# TPS54340_PS_and_Load_Rev3.net
KiCad netlist of a schematic drawn in EAGLE
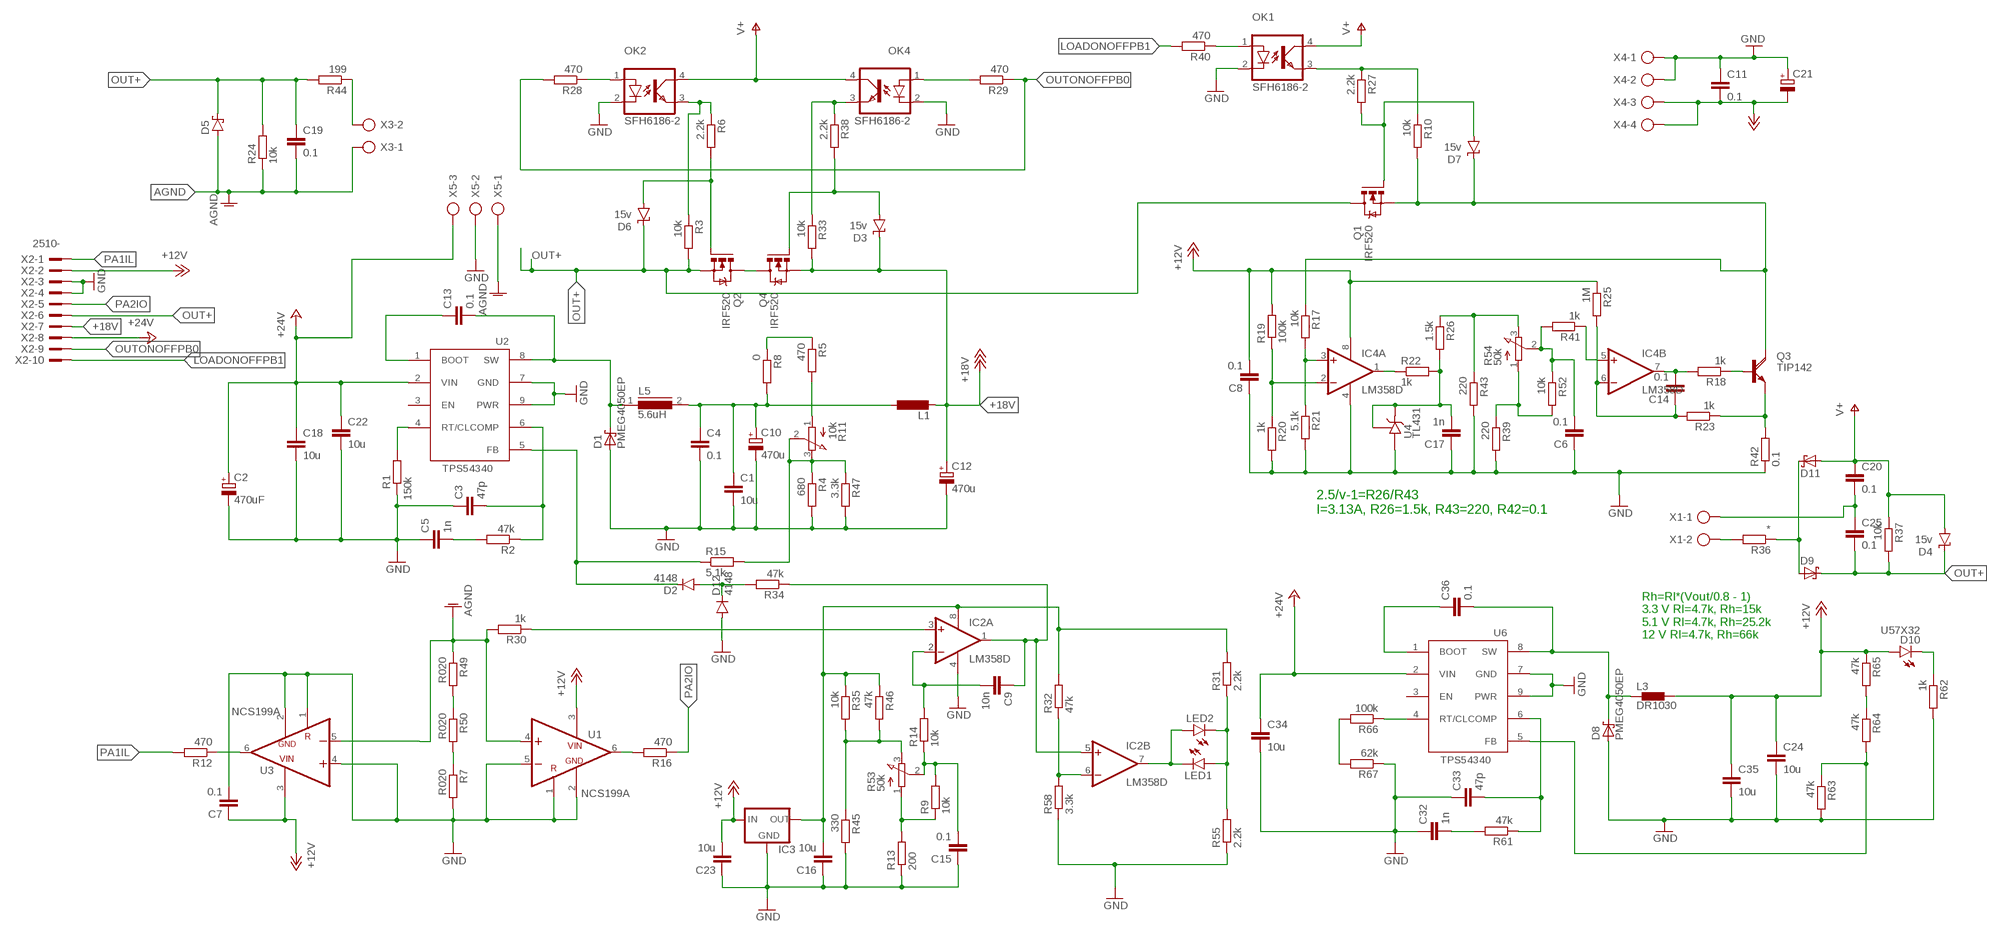
[diagram p0: schematic, sheet 1]

(export (version "E")
  (design (tool "Eeschema 10.0.6"))
  (components
    (comp (ref "C1")
      (value "10u")
      (footprint "eagle-import:C1210")
      (libsource (lib "eagle-import") (part "rcl_334_C-EUC1210"))
    )
    (comp (ref "C2")
      (value "470uF")
      (footprint "eagle-import:E5-10,5")
      (libsource (lib "eagle-import") (part "CPOL-EUE5-10.5"))
    )
    (comp (ref "C3")
      (value "47p")
      (footprint "eagle-import:C0603K")
      (libsource (lib "eagle-import") (part "rcl_334_C-EUC0603K"))
    )
    (comp (ref "C4")
      (value "0.1")
      (footprint "eagle-import:C1206")
      (libsource (lib "eagle-import") (part "C-EUC1206"))
    )
    (comp (ref "C5")
      (value "1n")
      (footprint "eagle-import:C0603K")
      (libsource (lib "eagle-import") (part "rcl_334_C-EUC0603K"))
    )
    (comp (ref "C6")
      (value "0.1")
      (footprint "eagle-import:C0603K")
      (libsource (lib "eagle-import") (part "rcl_334_C-EUC0603K"))
    )
    (comp (ref "C7")
      (value "0.1")
      (footprint "eagle-import:C0603K")
      (libsource (lib "eagle-import") (part "rcl_334_C-EUC0603K"))
    )
    (comp (ref "C8")
      (value "0.1")
      (footprint "eagle-import:C0603K")
      (libsource (lib "eagle-import") (part "rcl_334_C-EUC0603K"))
    )
    (comp (ref "C9")
      (value "10n")
      (footprint "eagle-import:C0603K")
      (libsource (lib "eagle-import") (part "rcl_334_C-EUC0603K"))
    )
    (comp (ref "C10")
      (value "470u")
      (footprint "eagle-import:E5-10,5")
      (libsource (lib "eagle-import") (part "CPOL-EUE5-10.5"))
    )
    (comp (ref "C11")
      (value "0.1")
      (footprint "eagle-import:C1206")
      (libsource (lib "eagle-import") (part "C-EUC1206"))
    )
    (comp (ref "C12")
      (value "470u")
      (footprint "eagle-import:E5-10,5")
      (libsource (lib "eagle-import") (part "CPOL-EUE5-10.5"))
    )
    (comp (ref "C13")
      (value "0.1")
      (footprint "eagle-import:C102-043X133")
      (libsource (lib "eagle-import") (part "rcl_334_C-EU102-043X133"))
    )
    (comp (ref "C14")
      (value "0.1")
      (footprint "eagle-import:C0603K")
      (libsource (lib "eagle-import") (part "rcl_334_C-EUC0603K"))
    )
    (comp (ref "C15")
      (value "0.1")
      (footprint "eagle-import:C0603K")
      (libsource (lib "eagle-import") (part "rcl_334_C-EUC0603K"))
    )
    (comp (ref "C16")
      (value "10u")
      (footprint "eagle-import:C0603K")
      (libsource (lib "eagle-import") (part "rcl_334_C-EUC0603K"))
    )
    (comp (ref "C17")
      (value "1n")
      (footprint "eagle-import:C0603K")
      (libsource (lib "eagle-import") (part "rcl_334_C-EUC0603K"))
    )
    (comp (ref "C18")
      (value "10u")
      (footprint "eagle-import:C1210")
      (libsource (lib "eagle-import") (part "rcl_334_C-EUC1210"))
    )
    (comp (ref "C19")
      (value "0.1")
      (footprint "eagle-import:C1206")
      (libsource (lib "eagle-import") (part "C-EUC1206"))
    )
    (comp (ref "C20")
      (value "0.1")
      (footprint "eagle-import:C1206")
      (libsource (lib "eagle-import") (part "C-EUC1206"))
    )
    (comp (ref "C21")
      (value "CPOL-EUE2.5-6")
      (footprint "eagle-import:E2,5-6")
      (libsource (lib "eagle-import") (part "CPOL-EUE2.5-6"))
    )
    (comp (ref "C22")
      (value "10u")
      (footprint "eagle-import:C1210")
      (libsource (lib "eagle-import") (part "rcl_334_C-EUC1210"))
    )
    (comp (ref "C23")
      (value "10u")
      (footprint "eagle-import:C0603K")
      (libsource (lib "eagle-import") (part "rcl_334_C-EUC0603K"))
    )
    (comp (ref "C24")
      (value "10u")
      (footprint "eagle-import:C1210")
      (libsource (lib "eagle-import") (part "rcl_334_C-EUC1210"))
    )
    (comp (ref "C25")
      (value "0.1")
      (footprint "eagle-import:C1206")
      (libsource (lib "eagle-import") (part "C-EUC1206"))
    )
    (comp (ref "C32")
      (value "1n")
      (footprint "eagle-import:C0603K")
      (libsource (lib "eagle-import") (part "rcl_334_C-EUC0603K"))
    )
    (comp (ref "C33")
      (value "47p")
      (footprint "eagle-import:C0603K")
      (libsource (lib "eagle-import") (part "rcl_334_C-EUC0603K"))
    )
    (comp (ref "C34")
      (value "10u")
      (footprint "eagle-import:C1210")
      (libsource (lib "eagle-import") (part "rcl_334_C-EUC1210"))
    )
    (comp (ref "C35")
      (value "10u")
      (footprint "eagle-import:C1206")
      (libsource (lib "eagle-import") (part "C-EUC1206"))
    )
    (comp (ref "C36")
      (value "0.1")
      (footprint "eagle-import:C102-043X133")
      (libsource (lib "eagle-import") (part "rcl_334_C-EU102-043X133"))
    )
    (comp (ref "D1")
      (value "PMEG4050EP")
      (footprint "eagle-import:SOD128")
      (libsource (lib "eagle-import") (part "PMEG4050EP"))
    )
    (comp (ref "D2")
      (value "4148")
      (footprint "eagle-import:SOD80C")
      (libsource (lib "eagle-import") (part "PMLL41SOD80C"))
    )
    (comp (ref "D3")
      (value "15v")
      (footprint "eagle-import:SMBJ")
      (libsource (lib "eagle-import") (part "SUPPRESSOR-SMBJ"))
    )
    (comp (ref "D4")
      (value "15v")
      (footprint "eagle-import:SMBJ")
      (libsource (lib "eagle-import") (part "SUPPRESSOR-SMBJ"))
    )
    (comp (ref "D5")
      (value "SCHOTTKY-DIODESMD")
      (footprint "eagle-import:SMB")
      (libsource (lib "eagle-import") (part "SCHOTTKY-DIODESMD"))
    )
    (comp (ref "D6")
      (value "15v")
      (footprint "eagle-import:SMBJ")
      (libsource (lib "eagle-import") (part "SUPPRESSOR-SMBJ"))
    )
    (comp (ref "D7")
      (value "15v")
      (footprint "eagle-import:SMBJ")
      (libsource (lib "eagle-import") (part "SUPPRESSOR-SMBJ"))
    )
    (comp (ref "D8")
      (value "PMEG4050EP")
      (footprint "eagle-import:SOD128")
      (libsource (lib "eagle-import") (part "PMEG4050EP"))
    )
    (comp (ref "D9")
      (value "PMEG4050EP")
      (footprint "eagle-import:SOD128")
      (libsource (lib "eagle-import") (part "PMEG4050EP"))
    )
    (comp (ref "D10")
      (value "U57X32")
      (footprint "eagle-import:U57X32")
      (libsource (lib "eagle-import") (part "U57X32"))
    )
    (comp (ref "D11")
      (value "PMEG4050EP")
      (footprint "eagle-import:SOD128")
      (libsource (lib "eagle-import") (part "PMEG4050EP"))
    )
    (comp (ref "D12")
      (value "4148")
      (footprint "eagle-import:SOD80C")
      (libsource (lib "eagle-import") (part "PMLL41SOD80C"))
    )
    (comp (ref "IC2")
      (value "LM358D")
      (footprint "eagle-import:SO08")
      (libsource (lib "eagle-import") (part "LM358D"))
    )
    (comp (ref "IC3")
      (value "LM1117")
      (footprint "eagle-import:SOT223")
      (libsource (lib "eagle-import") (part "LM1117"))
    )
    (comp (ref "IC4")
      (value "LM358D")
      (footprint "eagle-import:SO08")
      (libsource (lib "eagle-import") (part "LM358D"))
    )
    (comp (ref "L1")
      (value "L-EU0207/5V")
      (footprint "eagle-import:0207_5V")
      (libsource (lib "eagle-import") (part "L-EU0207/5V"))
    )
    (comp (ref "L3")
      (value "DR1030")
      (footprint "eagle-import:DR1030")
      (libsource (lib "eagle-import") (part "DR1030"))
    )
    (comp (ref "L5")
      (value "5.6uH")
      (footprint "eagle-import:DR125")
      (libsource (lib "eagle-import") (part "DR125"))
    )
    (comp (ref "LED1")
      (value "LEDB152")
      (footprint "eagle-import:Q62902-B152")
      (libsource (lib "eagle-import") (part "LEDB152"))
    )
    (comp (ref "LED2")
      (value "LEDB152")
      (footprint "eagle-import:Q62902-B152")
      (libsource (lib "eagle-import") (part "LEDB152"))
    )
    (comp (ref "OK1")
      (value "SFH6186-2")
      (footprint "eagle-import:SMD4-7")
      (fields (field (name "MF") "VISHAY/TELEFUNKEN"))
      (libsource (lib "eagle-import") (part "SFH618?6-2"))
    )
    (comp (ref "OK2")
      (value "SFH6186-2")
      (footprint "eagle-import:SMD4-7")
      (fields (field (name "MF") "VISHAY/TELEFUNKEN"))
      (libsource (lib "eagle-import") (part "SFH618?6-2"))
    )
    (comp (ref "OK4")
      (value "SFH6186-2")
      (footprint "eagle-import:SMD4-7")
      (fields (field (name "MF") "VISHAY/TELEFUNKEN"))
      (libsource (lib "eagle-import") (part "SFH618?6-2"))
    )
    (comp (ref "Q1")
      (value "IRF520")
      (footprint "eagle-import:TO220BV")
      (libsource (lib "eagle-import") (part "IRF520"))
    )
    (comp (ref "Q2")
      (value "IRF520")
      (footprint "eagle-import:TO220BV")
      (libsource (lib "eagle-import") (part "IRF520"))
    )
    (comp (ref "Q3")
      (value "TIP142")
      (footprint "eagle-import:SOT93")
      (libsource (lib "eagle-import") (part "TIP142"))
    )
    (comp (ref "Q4")
      (value "IRF520")
      (footprint "eagle-import:TO220BV")
      (libsource (lib "eagle-import") (part "IRF520"))
    )
    (comp (ref "R1")
      (value "150k")
      (footprint "eagle-import:R1206")
      (libsource (lib "eagle-import") (part "R-EU_R1206"))
    )
    (comp (ref "R2")
      (value "47k")
      (footprint "eagle-import:R0603")
      (libsource (lib "eagle-import") (part "rcl_334_R-EU_R0603"))
    )
    (comp (ref "R3")
      (value "10k")
      (footprint "eagle-import:R0603")
      (libsource (lib "eagle-import") (part "rcl_334_R-EU_R0603"))
    )
    (comp (ref "R4")
      (value "680")
      (footprint "eagle-import:R1206")
      (libsource (lib "eagle-import") (part "R-EU_R1206"))
    )
    (comp (ref "R5")
      (value "470")
      (footprint "eagle-import:R1206")
      (libsource (lib "eagle-import") (part "R-EU_R1206"))
    )
    (comp (ref "R6")
      (value "2.2k")
      (footprint "eagle-import:R0603")
      (libsource (lib "eagle-import") (part "rcl_334_R-EU_R0603"))
    )
    (comp (ref "R7")
      (value "R020")
      (footprint "eagle-import:R1206")
      (libsource (lib "eagle-import") (part "R-EU_R1206"))
    )
    (comp (ref "R8")
      (value "0")
      (footprint "eagle-import:R0603")
      (libsource (lib "eagle-import") (part "rcl_334_R-EU_R0603"))
    )
    (comp (ref "R9")
      (value "10k")
      (footprint "eagle-import:R0603")
      (libsource (lib "eagle-import") (part "rcl_334_R-EU_R0603"))
    )
    (comp (ref "R10")
      (value "10k")
      (footprint "eagle-import:R0603")
      (libsource (lib "eagle-import") (part "rcl_334_R-EU_R0603"))
    )
    (comp (ref "R11")
      (value "10k")
      (footprint "eagle-import:3RP_1610N")
      (libsource (lib "eagle-import") (part "3RP/1610N"))
    )
    (comp (ref "R12")
      (value "470")
      (footprint "eagle-import:R0603")
      (libsource (lib "eagle-import") (part "rcl_334_R-EU_R0603"))
    )
    (comp (ref "R13")
      (value "200")
      (footprint "eagle-import:R0603")
      (libsource (lib "eagle-import") (part "rcl_334_R-EU_R0603"))
    )
    (comp (ref "R14")
      (value "10k")
      (footprint "eagle-import:R1206")
      (libsource (lib "eagle-import") (part "R-EU_R1206"))
    )
    (comp (ref "R15")
      (value "5.1k")
      (footprint "eagle-import:R0603")
      (libsource (lib "eagle-import") (part "rcl_334_R-EU_R0603"))
    )
    (comp (ref "R16")
      (value "470")
      (footprint "eagle-import:R1206")
      (libsource (lib "eagle-import") (part "R-EU_R1206"))
    )
    (comp (ref "R17")
      (value "10k")
      (footprint "eagle-import:R0603")
      (libsource (lib "eagle-import") (part "rcl_334_R-EU_R0603"))
    )
    (comp (ref "R18")
      (value "1k")
      (footprint "eagle-import:R0603")
      (libsource (lib "eagle-import") (part "rcl_334_R-EU_R0603"))
    )
    (comp (ref "R19")
      (value "100k")
      (footprint "eagle-import:R1206")
      (libsource (lib "eagle-import") (part "R-EU_R1206"))
    )
    (comp (ref "R20")
      (value "1k")
      (footprint "eagle-import:R0603")
      (libsource (lib "eagle-import") (part "rcl_334_R-EU_R0603"))
    )
    (comp (ref "R21")
      (value "5.1k")
      (footprint "eagle-import:R0603")
      (libsource (lib "eagle-import") (part "rcl_334_R-EU_R0603"))
    )
    (comp (ref "R22")
      (value "1k")
      (footprint "eagle-import:R0603")
      (libsource (lib "eagle-import") (part "rcl_334_R-EU_R0603"))
    )
    (comp (ref "R23")
      (value "1k")
      (footprint "eagle-import:R0603")
      (libsource (lib "eagle-import") (part "rcl_334_R-EU_R0603"))
    )
    (comp (ref "R24")
      (value "10k")
      (footprint "eagle-import:R1206")
      (libsource (lib "eagle-import") (part "R-EU_R1206"))
    )
    (comp (ref "R25")
      (value "1M")
      (footprint "eagle-import:R1206")
      (libsource (lib "eagle-import") (part "R-EU_R1206"))
    )
    (comp (ref "R26")
      (value "1.5k")
      (footprint "eagle-import:R0603")
      (libsource (lib "eagle-import") (part "rcl_334_R-EU_R0603"))
    )
    (comp (ref "R27")
      (value "2.2k")
      (footprint "eagle-import:R0603")
      (libsource (lib "eagle-import") (part "rcl_334_R-EU_R0603"))
    )
    (comp (ref "R28")
      (value "470")
      (footprint "eagle-import:R0603")
      (libsource (lib "eagle-import") (part "rcl_334_R-EU_R0603"))
    )
    (comp (ref "R29")
      (value "470")
      (footprint "eagle-import:R0603")
      (libsource (lib "eagle-import") (part "rcl_334_R-EU_R0603"))
    )
    (comp (ref "R30")
      (value "1k")
      (footprint "eagle-import:R0603")
      (libsource (lib "eagle-import") (part "rcl_334_R-EU_R0603"))
    )
    (comp (ref "R31")
      (value "2.2k")
      (footprint "eagle-import:R0603")
      (libsource (lib "eagle-import") (part "rcl_334_R-EU_R0603"))
    )
    (comp (ref "R32")
      (value "47k")
      (footprint "eagle-import:R0603")
      (libsource (lib "eagle-import") (part "rcl_334_R-EU_R0603"))
    )
    (comp (ref "R33")
      (value "10k")
      (footprint "eagle-import:R0603")
      (libsource (lib "eagle-import") (part "rcl_334_R-EU_R0603"))
    )
    (comp (ref "R34")
      (value "47k")
      (footprint "eagle-import:R0603")
      (libsource (lib "eagle-import") (part "rcl_334_R-EU_R0603"))
    )
    (comp (ref "R35")
      (value "10k")
      (footprint "eagle-import:R0603")
      (libsource (lib "eagle-import") (part "rcl_334_R-EU_R0603"))
    )
    (comp (ref "R36")
      (value "*")
      (footprint "eagle-import:R1206")
      (libsource (lib "eagle-import") (part "R-EU_R1206"))
    )
    (comp (ref "R37")
      (value "10k")
      (footprint "eagle-import:R1206")
      (libsource (lib "eagle-import") (part "R-EU_R1206"))
    )
    (comp (ref "R38")
      (value "2.2k")
      (footprint "eagle-import:R0603")
      (libsource (lib "eagle-import") (part "rcl_334_R-EU_R0603"))
    )
    (comp (ref "R39")
      (value "220")
      (footprint "eagle-import:R0603")
      (libsource (lib "eagle-import") (part "rcl_334_R-EU_R0603"))
    )
    (comp (ref "R40")
      (value "470")
      (footprint "eagle-import:R0603")
      (libsource (lib "eagle-import") (part "rcl_334_R-EU_R0603"))
    )
    (comp (ref "R41")
      (value "1k")
      (footprint "eagle-import:R1206")
      (libsource (lib "eagle-import") (part "R-EU_R1206"))
    )
    (comp (ref "R42")
      (value "0.1")
      (footprint "eagle-import:0414_15")
      (libsource (lib "eagle-import") (part "rcl_334_R-EU_0414/15"))
    )
    (comp (ref "R43")
      (value "220")
      (footprint "eagle-import:R0603")
      (libsource (lib "eagle-import") (part "rcl_334_R-EU_R0603"))
    )
    (comp (ref "R44")
      (value "199")
      (footprint "eagle-import:R0603")
      (libsource (lib "eagle-import") (part "rcl_334_R-EU_R0603"))
    )
    (comp (ref "R45")
      (value "330")
      (footprint "eagle-import:R0603")
      (libsource (lib "eagle-import") (part "rcl_334_R-EU_R0603"))
    )
    (comp (ref "R46")
      (value "47k")
      (footprint "eagle-import:R0603")
      (libsource (lib "eagle-import") (part "rcl_334_R-EU_R0603"))
    )
    (comp (ref "R47")
      (value "3.3k")
      (footprint "eagle-import:R1206")
      (libsource (lib "eagle-import") (part "R-EU_R1206"))
    )
    (comp (ref "R49")
      (value "R020")
      (footprint "eagle-import:R1206")
      (libsource (lib "eagle-import") (part "R-EU_R1206"))
    )
    (comp (ref "R50")
      (value "R020")
      (footprint "eagle-import:R1206")
      (libsource (lib "eagle-import") (part "R-EU_R1206"))
    )
    (comp (ref "R52")
      (value "10k")
      (footprint "eagle-import:R0603")
      (libsource (lib "eagle-import") (part "rcl_334_R-EU_R0603"))
    )
    (comp (ref "R53")
      (value "50k")
      (footprint "eagle-import:3RP_1610N")
      (libsource (lib "eagle-import") (part "3RP/1610N"))
    )
    (comp (ref "R54")
      (value "50k")
      (footprint "eagle-import:3RP_1610N")
      (libsource (lib "eagle-import") (part "3RP/1610N"))
    )
    (comp (ref "R55")
      (value "2.2k")
      (footprint "eagle-import:R0603")
      (libsource (lib "eagle-import") (part "rcl_334_R-EU_R0603"))
    )
    (comp (ref "R58")
      (value "3.3k")
      (footprint "eagle-import:R0603")
      (libsource (lib "eagle-import") (part "rcl_334_R-EU_R0603"))
    )
    (comp (ref "R61")
      (value "47k")
      (footprint "eagle-import:R0603")
      (libsource (lib "eagle-import") (part "rcl_334_R-EU_R0603"))
    )
    (comp (ref "R62")
      (value "1k")
      (footprint "eagle-import:R0603")
      (libsource (lib "eagle-import") (part "rcl_334_R-EU_R0603"))
    )
    (comp (ref "R63")
      (value "47k")
      (footprint "eagle-import:R0603")
      (libsource (lib "eagle-import") (part "rcl_334_R-EU_R0603"))
    )
    (comp (ref "R64")
      (value "47k")
      (footprint "eagle-import:R0603")
      (libsource (lib "eagle-import") (part "rcl_334_R-EU_R0603"))
    )
    (comp (ref "R65")
      (value "47k")
      (footprint "eagle-import:R0603")
      (libsource (lib "eagle-import") (part "rcl_334_R-EU_R0603"))
    )
    (comp (ref "R66")
      (value "100k")
      (footprint "eagle-import:R0603")
      (libsource (lib "eagle-import") (part "rcl_334_R-EU_R0603"))
    )
    (comp (ref "R67")
      (value "62k")
      (footprint "eagle-import:R0603")
      (libsource (lib "eagle-import") (part "rcl_334_R-EU_R0603"))
    )
    (comp (ref "U1")
      (value "NCS199A")
      (footprint "eagle-import:SOT363")
      (libsource (lib "eagle-import") (part "NCS199A"))
    )
    (comp (ref "U2")
      (value "TPS54340")
      (footprint "eagle-import:HSOP")
      (libsource (lib "eagle-import") (part "TPS54340SO8"))
    )
    (comp (ref "U3")
      (value "NCS199A")
      (footprint "eagle-import:SOT363")
      (libsource (lib "eagle-import") (part "NCS199A"))
    )
    (comp (ref "U4")
      (value "TL431")
      (footprint "eagle-import:SOT23")
      (libsource (lib "eagle-import") (part "TL431"))
    )
    (comp (ref "U6")
      (value "TPS54340SO8")
      (footprint "eagle-import:HSOP")
      (libsource (lib "eagle-import") (part "TPS54340SO8"))
    )
    (comp (ref "X1")
      (value "AK500/2")
      (footprint "eagle-import:AK500_2")
      (libsource (lib "eagle-import") (part "AK500/2"))
    )
    (comp (ref "X2")
      (value "2510-")
      (footprint "eagle-import:PAK100_2500-10")
      (fields (field (name "MF") "3M") (field (name "MPN") "2510-6002UB"))
      (libsource (lib "eagle-import") (part "2510-"))
    )
    (comp (ref "X3")
      (value "AK500/2")
      (footprint "eagle-import:AK500_2")
      (libsource (lib "eagle-import") (part "AK500/2"))
    )
    (comp (ref "X4")
      (value "AK500/4")
      (footprint "eagle-import:AK500_4")
      (libsource (lib "eagle-import") (part "AK500/4"))
    )
    (comp (ref "X5")
      (value "AK500/3")
      (footprint "eagle-import:AK500_3")
      (libsource (lib "eagle-import") (part "AK500/3"))
    )
  )
  (nets
    (net (code "1") (name "+12V") (class "Default")
      (node (ref "C11") (pin "2") (pinfunction "2_2") (pintype "passive"))
      (node (ref "C21") (pin "-") (pinfunction "-_-") (pintype "passive"))
      (node (ref "C23") (pin "2") (pinfunction "2_2") (pintype "passive"))
      (node (ref "C24") (pin "1") (pinfunction "1_1") (pintype "passive"))
      (node (ref "C35") (pin "1") (pinfunction "1_1") (pintype "passive"))
      (node (ref "C7") (pin "1") (pinfunction "1_1") (pintype "passive"))
      (node (ref "C8") (pin "2") (pinfunction "2_2") (pintype "passive"))
      (node (ref "D10") (pin "A") (pinfunction "A_A") (pintype "passive"))
      (node (ref "IC3") (pin "3") (pinfunction "IN_3") (pintype "input"))
      (node (ref "IC4") (pin "8") (pinfunction "V+_8") (pintype "power_in"))
      (node (ref "L3") (pin "2") (pinfunction "2_2") (pintype "passive"))
      (node (ref "R19") (pin "2") (pinfunction "2_2") (pintype "passive"))
      (node (ref "R25") (pin "1") (pinfunction "1_1") (pintype "passive"))
      (node (ref "R65") (pin "1") (pinfunction "1_1") (pintype "passive"))
      (node (ref "U1") (pin "3") (pinfunction "VCC_3") (pintype "power_in"))
      (node (ref "U3") (pin "3") (pinfunction "VCC_3") (pintype "power_in"))
      (node (ref "X2") (pin "2") (pinfunction "KL_2") (pintype "passive"))
      (node (ref "X4") (pin "3") (pinfunction "KL_3") (pintype "passive"))
      (node (ref "X4") (pin "4") (pinfunction "KL_4") (pintype "passive"))
    )
    (net (code "2") (name "+18V") (class "Default")
      (node (ref "C12") (pin "+") (pinfunction "+_+") (pintype "passive"))
      (node (ref "D3") (pin "C") (pinfunction "C_C") (pintype "passive"))
      (node (ref "L1") (pin "2") (pinfunction "2_2") (pintype "passive"))
      (node (ref "Q4") (pin "S") (pinfunction "S_S") (pintype "passive"))
      (node (ref "R33") (pin "2") (pinfunction "2_2") (pintype "passive"))
      (node (ref "X2") (pin "7") (pinfunction "KL_7") (pintype "passive"))
    )
    (net (code "3") (name "+24V") (class "Default")
      (node (ref "C18") (pin "1") (pinfunction "1_1") (pintype "passive"))
      (node (ref "C2") (pin "+") (pinfunction "+_+") (pintype "passive"))
      (node (ref "C22") (pin "1") (pinfunction "1_1") (pintype "passive"))
      (node (ref "C34") (pin "1") (pinfunction "1_1") (pintype "passive"))
      (node (ref "U2") (pin "2") (pinfunction "VIN_2") (pintype "power_in"))
      (node (ref "U6") (pin "2") (pinfunction "VIN_2") (pintype "power_in"))
      (node (ref "X2") (pin "8") (pinfunction "KL_8") (pintype "passive"))
      (node (ref "X5") (pin "3") (pinfunction "KL_3") (pintype "passive"))
    )
    (net (code "4") (name "AGND") (class "Default")
      (node (ref "C19") (pin "2") (pinfunction "2_2") (pintype "passive"))
      (node (ref "D5") (pin "A") (pinfunction "A_A") (pintype "passive"))
      (node (ref "R24") (pin "1") (pinfunction "1_1") (pintype "passive"))
      (node (ref "R30") (pin "2") (pinfunction "2_2") (pintype "passive"))
      (node (ref "R49") (pin "1") (pinfunction "1_1") (pintype "passive"))
      (node (ref "U1") (pin "4") (pinfunction "IN+_4") (pintype "input"))
      (node (ref "U3") (pin "5") (pinfunction "IN-_5") (pintype "input"))
      (node (ref "X3") (pin "1") (pinfunction "KL_1") (pintype "passive"))
      (node (ref "X5") (pin "1") (pinfunction "KL_1") (pintype "passive"))
    )
    (net (code "5") (name "GND") (class "Default")
      (node (ref "C1") (pin "2") (pinfunction "2_2") (pintype "passive"))
      (node (ref "C10") (pin "-") (pinfunction "-_-") (pintype "passive"))
      (node (ref "C11") (pin "1") (pinfunction "1_1") (pintype "passive"))
      (node (ref "C12") (pin "-") (pinfunction "-_-") (pintype "passive"))
      (node (ref "C15") (pin "1") (pinfunction "1_1") (pintype "passive"))
      (node (ref "C16") (pin "1") (pinfunction "1_1") (pintype "passive"))
      (node (ref "C17") (pin "1") (pinfunction "1_1") (pintype "passive"))
      (node (ref "C18") (pin "2") (pinfunction "2_2") (pintype "passive"))
      (node (ref "C2") (pin "-") (pinfunction "-_-") (pintype "passive"))
      (node (ref "C21") (pin "+") (pinfunction "+_+") (pintype "passive"))
      (node (ref "C22") (pin "2") (pinfunction "2_2") (pintype "passive"))
      (node (ref "C23") (pin "1") (pinfunction "1_1") (pintype "passive"))
      (node (ref "C24") (pin "2") (pinfunction "2_2") (pintype "passive"))
      (node (ref "C3") (pin "1") (pinfunction "1_1") (pintype "passive"))
      (node (ref "C32") (pin "1") (pinfunction "1_1") (pintype "passive"))
      (node (ref "C33") (pin "1") (pinfunction "1_1") (pintype "passive"))
      (node (ref "C34") (pin "2") (pinfunction "2_2") (pintype "passive"))
      (node (ref "C35") (pin "2") (pinfunction "2_2") (pintype "passive"))
      (node (ref "C4") (pin "2") (pinfunction "2_2") (pintype "passive"))
      (node (ref "C5") (pin "1") (pinfunction "1_1") (pintype "passive"))
      (node (ref "C6") (pin "1") (pinfunction "1_1") (pintype "passive"))
      (node (ref "C7") (pin "2") (pinfunction "2_2") (pintype "passive"))
      (node (ref "C8") (pin "1") (pinfunction "1_1") (pintype "passive"))
      (node (ref "D1") (pin "2") (pinfunction "A_2") (pintype "passive"))
      (node (ref "D12") (pin "A") (pinfunction "A_A") (pintype "passive"))
      (node (ref "D8") (pin "2") (pinfunction "A_2") (pintype "passive"))
      (node (ref "IC2") (pin "4") (pinfunction "V-_4") (pintype "power_in"))
      (node (ref "IC3") (pin "1") (pinfunction "GND_1") (pintype "input"))
      (node (ref "IC4") (pin "4") (pinfunction "V-_4") (pintype "power_in"))
      (node (ref "OK1") (pin "2") (pinfunction "C_2") (pintype "passive"))
      (node (ref "OK2") (pin "2") (pinfunction "C_2") (pintype "passive"))
      (node (ref "OK4") (pin "2") (pinfunction "C_2") (pintype "passive"))
      (node (ref "R1") (pin "1") (pinfunction "1_1") (pintype "passive"))
      (node (ref "R13") (pin "1") (pinfunction "1_1") (pintype "passive"))
      (node (ref "R20") (pin "2") (pinfunction "2_2") (pintype "passive"))
      (node (ref "R21") (pin "2") (pinfunction "2_2") (pintype "passive"))
      (node (ref "R39") (pin "2") (pinfunction "2_2") (pintype "passive"))
      (node (ref "R4") (pin "2") (pinfunction "2_2") (pintype "passive"))
      (node (ref "R42") (pin "1") (pinfunction "1_1") (pintype "passive"))
      (node (ref "R43") (pin "2") (pinfunction "2_2") (pintype "passive"))
      (node (ref "R45") (pin "2") (pinfunction "2_2") (pintype "passive"))
      (node (ref "R47") (pin "2") (pinfunction "2_2") (pintype "passive"))
      (node (ref "R55") (pin "1") (pinfunction "1_1") (pintype "passive"))
      (node (ref "R58") (pin "1") (pinfunction "1_1") (pintype "passive"))
      (node (ref "R62") (pin "2") (pinfunction "2_2") (pintype "passive"))
      (node (ref "R63") (pin "2") (pinfunction "2_2") (pintype "passive"))
      (node (ref "R67") (pin "1") (pinfunction "1_1") (pintype "passive"))
      (node (ref "R7") (pin "2") (pinfunction "2_2") (pintype "passive"))
      (node (ref "U1") (pin "1") (pinfunction "REF_1") (pintype "input"))
      (node (ref "U1") (pin "2") (pinfunction "GND_2") (pintype "power_in"))
      (node (ref "U1") (pin "5") (pinfunction "IN-_5") (pintype "input"))
      (node (ref "U2") (pin "7") (pinfunction "GND_7") (pintype "power_in"))
      (node (ref "U2") (pin "9") (pinfunction "PWR_9") (pintype "power_in"))
      (node (ref "U3") (pin "1") (pinfunction "REF_1") (pintype "input"))
      (node (ref "U3") (pin "2") (pinfunction "GND_2") (pintype "power_in"))
      (node (ref "U3") (pin "4") (pinfunction "IN+_4") (pintype "input"))
      (node (ref "U4") (pin "3") (pinfunction "A_3") (pintype "passive"))
      (node (ref "U6") (pin "7") (pinfunction "GND_7") (pintype "power_in"))
      (node (ref "U6") (pin "9") (pinfunction "PWR_9") (pintype "power_in"))
      (node (ref "X2") (pin "3") (pinfunction "KL_3") (pintype "passive"))
      (node (ref "X2") (pin "4") (pinfunction "KL_4") (pintype "passive"))
      (node (ref "X4") (pin "1") (pinfunction "KL_1") (pintype "passive"))
      (node (ref "X4") (pin "2") (pinfunction "KL_2") (pintype "passive"))
      (node (ref "X5") (pin "2") (pinfunction "KL_2") (pintype "passive"))
    )
    (net (code "6") (name "LOADONOFFPB1") (class "Default")
      (node (ref "R40") (pin "2") (pinfunction "2_2") (pintype "passive"))
      (node (ref "X2") (pin "10") (pinfunction "KL_10") (pintype "passive"))
    )
    (net (code "7") (name "Net-(C1-Pad1)") (class "Default")
      (node (ref "C1") (pin "1") (pinfunction "1_1") (pintype "passive"))
      (node (ref "C10") (pin "+") (pinfunction "+_+") (pintype "passive"))
      (node (ref "C4") (pin "1") (pinfunction "1_1") (pintype "passive"))
      (node (ref "L1") (pin "1") (pinfunction "1_1") (pintype "passive"))
      (node (ref "L5") (pin "2") (pinfunction "2_2") (pintype "passive"))
      (node (ref "R8") (pin "2") (pinfunction "2_2") (pintype "passive"))
    )
    (net (code "8") (name "Net-(C5-Pad2)") (class "Default")
      (node (ref "C5") (pin "2") (pinfunction "2_2") (pintype "passive"))
      (node (ref "R2") (pin "2") (pinfunction "2_2") (pintype "passive"))
    )
    (net (code "9") (name "Net-(C32-Pad2)") (class "Default")
      (node (ref "C32") (pin "2") (pinfunction "2_2") (pintype "passive"))
      (node (ref "R61") (pin "2") (pinfunction "2_2") (pintype "passive"))
    )
    (net (code "10") (name "Net-(D1-K)") (class "Default")
      (node (ref "C13") (pin "2") (pinfunction "2_2") (pintype "passive"))
      (node (ref "D1") (pin "1") (pinfunction "K_1") (pintype "passive"))
      (node (ref "L5") (pin "1") (pinfunction "1_1") (pintype "passive"))
      (node (ref "U2") (pin "8") (pinfunction "SW_8") (pintype "power_in"))
    )
    (net (code "11") (name "Net-(D3-PadA)") (class "Default")
      (node (ref "D3") (pin "A") (pinfunction "A_A") (pintype "passive"))
      (node (ref "Q4") (pin "G") (pinfunction "G_G") (pintype "passive"))
      (node (ref "R38") (pin "2") (pinfunction "2_2") (pintype "passive"))
    )
    (net (code "12") (name "Net-(D6-PadA)") (class "Default")
      (node (ref "D6") (pin "A") (pinfunction "A_A") (pintype "passive"))
      (node (ref "Q2") (pin "G") (pinfunction "G_G") (pintype "passive"))
      (node (ref "R6") (pin "2") (pinfunction "2_2") (pintype "passive"))
    )
    (net (code "13") (name "Net-(D7-PadA)") (class "Default")
      (node (ref "D7") (pin "A") (pinfunction "A_A") (pintype "passive"))
      (node (ref "Q1") (pin "G") (pinfunction "G_G") (pintype "passive"))
      (node (ref "R27") (pin "2") (pinfunction "2_2") (pintype "passive"))
    )
    (net (code "14") (name "Net-(D7-PadC)") (class "Default")
      (node (ref "D7") (pin "C") (pinfunction "C_C") (pintype "passive"))
      (node (ref "Q1") (pin "S") (pinfunction "S_S") (pintype "passive"))
      (node (ref "Q3") (pin "C") (pinfunction "C_C") (pintype "passive"))
      (node (ref "R10") (pin "2") (pinfunction "2_2") (pintype "passive"))
      (node (ref "R17") (pin "1") (pinfunction "1_1") (pintype "passive"))
    )
    (net (code "15") (name "Net-(D8-K)") (class "Default")
      (node (ref "C36") (pin "2") (pinfunction "2_2") (pintype "passive"))
      (node (ref "D8") (pin "1") (pinfunction "K_1") (pintype "passive"))
      (node (ref "L3") (pin "1") (pinfunction "1_1") (pintype "passive"))
      (node (ref "U6") (pin "8") (pinfunction "SW_8") (pintype "power_in"))
    )
    (net (code "16") (name "Net-(D10-C)") (class "Default")
      (node (ref "D10") (pin "K") (pinfunction "C_K") (pintype "passive"))
      (node (ref "R62") (pin "1") (pinfunction "1_1") (pintype "passive"))
    )
    (net (code "17") (name "Net-(D11-K)") (class "Default")
      (node (ref "D11") (pin "1") (pinfunction "K_1") (pintype "passive"))
      (node (ref "D9") (pin "2") (pinfunction "A_2") (pintype "passive"))
      (node (ref "R36") (pin "1") (pinfunction "1_1") (pintype "passive"))
    )
    (net (code "18") (name "Net-(D12-PadC)") (class "Default")
      (node (ref "D12") (pin "C") (pinfunction "C_C") (pintype "passive"))
      (node (ref "D2") (pin "A") (pinfunction "A_A") (pintype "passive"))
      (node (ref "R34") (pin "2") (pinfunction "2_2") (pintype "passive"))
    )
    (net (code "19") (name "Net-(IC2A-+IN)") (class "Default")
      (node (ref "IC2") (pin "3") (pinfunction "+IN_3") (pintype "input"))
      (node (ref "R30") (pin "1") (pinfunction "1_1") (pintype "passive"))
    )
    (net (code "20") (name "Net-(IC2A--IN)") (class "Default")
      (node (ref "C9") (pin "2") (pinfunction "2_2") (pintype "passive"))
      (node (ref "IC2") (pin "2") (pinfunction "-IN_2") (pintype "input"))
      (node (ref "R14") (pin "2") (pinfunction "2_2") (pintype "passive"))
    )
    (net (code "21") (name "Net-(IC2A-OUT)") (class "Default")
      (node (ref "C9") (pin "1") (pinfunction "1_1") (pintype "passive"))
      (node (ref "IC2") (pin "1") (pinfunction "OUT_1") (pintype "output"))
      (node (ref "IC2") (pin "5") (pinfunction "+IN_5") (pintype "input"))
      (node (ref "R34") (pin "1") (pinfunction "1_1") (pintype "passive"))
    )
    (net (code "22") (name "Net-(IC2B--IN)") (class "Default")
      (node (ref "IC2") (pin "6") (pinfunction "-IN_6") (pintype "input"))
      (node (ref "R32") (pin "1") (pinfunction "1_1") (pintype "passive"))
      (node (ref "R58") (pin "2") (pinfunction "2_2") (pintype "passive"))
    )
    (net (code "23") (name "Net-(IC2B-OUT)") (class "Default")
      (node (ref "IC2") (pin "7") (pinfunction "OUT_7") (pintype "output"))
      (node (ref "LED1") (pin "K") (pinfunction "C_K") (pintype "passive"))
      (node (ref "LED2") (pin "A") (pinfunction "A_A") (pintype "passive"))
    )
    (net (code "24") (name "Net-(IC2C-V+)") (class "Default")
      (node (ref "C16") (pin "2") (pinfunction "2_2") (pintype "passive"))
      (node (ref "IC2") (pin "8") (pinfunction "V+_8") (pintype "power_in"))
      (node (ref "IC3") (pin "2") (pinfunction "OUT_2") (pintype "passive"))
      (node (ref "IC3") (pin "4") (pinfunction "OUT_4") (pintype "passive"))
      (node (ref "R31") (pin "2") (pinfunction "2_2") (pintype "passive"))
      (node (ref "R32") (pin "2") (pinfunction "2_2") (pintype "passive"))
      (node (ref "R35") (pin "1") (pinfunction "1_1") (pintype "passive"))
      (node (ref "R46") (pin "1") (pinfunction "1_1") (pintype "passive"))
    )
    (net (code "25") (name "Net-(IC4A-+IN)") (class "Default")
      (node (ref "IC4") (pin "3") (pinfunction "+IN_3") (pintype "input"))
      (node (ref "R17") (pin "2") (pinfunction "2_2") (pintype "passive"))
      (node (ref "R21") (pin "1") (pinfunction "1_1") (pintype "passive"))
    )
    (net (code "26") (name "Net-(IC4A--IN)") (class "Default")
      (node (ref "IC4") (pin "2") (pinfunction "-IN_2") (pintype "input"))
      (node (ref "R19") (pin "1") (pinfunction "1_1") (pintype "passive"))
      (node (ref "R20") (pin "1") (pinfunction "1_1") (pintype "passive"))
    )
    (net (code "27") (name "Net-(IC4A-OUT)") (class "Default")
      (node (ref "IC4") (pin "1") (pinfunction "OUT_1") (pintype "output"))
      (node (ref "R22") (pin "1") (pinfunction "1_1") (pintype "passive"))
    )
    (net (code "28") (name "Net-(IC4B-+IN)") (class "Default")
      (node (ref "IC4") (pin "5") (pinfunction "+IN_5") (pintype "input"))
      (node (ref "R41") (pin "1") (pinfunction "1_1") (pintype "passive"))
    )
    (net (code "29") (name "Net-(IC4B--IN)") (class "Default")
      (node (ref "C14") (pin "1") (pinfunction "1_1") (pintype "passive"))
      (node (ref "IC4") (pin "6") (pinfunction "-IN_6") (pintype "input"))
      (node (ref "R23") (pin "2") (pinfunction "2_2") (pintype "passive"))
      (node (ref "R25") (pin "2") (pinfunction "2_2") (pintype "passive"))
    )
    (net (code "30") (name "Net-(IC4B-OUT)") (class "Default")
      (node (ref "C14") (pin "2") (pinfunction "2_2") (pintype "passive"))
      (node (ref "IC4") (pin "7") (pinfunction "OUT_7") (pintype "output"))
      (node (ref "R18") (pin "2") (pinfunction "2_2") (pintype "passive"))
    )
    (net (code "31") (name "Net-(LED2-C)") (class "Default")
      (node (ref "LED1") (pin "A") (pinfunction "A_A") (pintype "passive"))
      (node (ref "LED2") (pin "K") (pinfunction "C_K") (pintype "passive"))
      (node (ref "R31") (pin "1") (pinfunction "1_1") (pintype "passive"))
      (node (ref "R55") (pin "2") (pinfunction "2_2") (pintype "passive"))
    )
    (net (code "32") (name "Net-(OK1-A)") (class "Default")
      (node (ref "OK1") (pin "1") (pinfunction "A_1") (pintype "passive"))
      (node (ref "R40") (pin "1") (pinfunction "1_1") (pintype "passive"))
    )
    (net (code "33") (name "Net-(OK1-EMIT)") (class "Default")
      (node (ref "OK1") (pin "3") (pinfunction "EMIT_3") (pintype "passive"))
      (node (ref "R10") (pin "1") (pinfunction "1_1") (pintype "passive"))
      (node (ref "R27") (pin "1") (pinfunction "1_1") (pintype "passive"))
    )
    (net (code "34") (name "Net-(OK2-A)") (class "Default")
      (node (ref "OK2") (pin "1") (pinfunction "A_1") (pintype "passive"))
      (node (ref "R28") (pin "1") (pinfunction "1_1") (pintype "passive"))
    )
    (net (code "35") (name "Net-(OK2-EMIT)") (class "Default")
      (node (ref "OK2") (pin "3") (pinfunction "EMIT_3") (pintype "passive"))
      (node (ref "R3") (pin "1") (pinfunction "1_1") (pintype "passive"))
      (node (ref "R6") (pin "1") (pinfunction "1_1") (pintype "passive"))
    )
    (net (code "36") (name "Net-(OK4-A)") (class "Default")
      (node (ref "OK4") (pin "1") (pinfunction "A_1") (pintype "passive"))
      (node (ref "R29") (pin "2") (pinfunction "2_2") (pintype "passive"))
    )
    (net (code "37") (name "Net-(OK4-EMIT)") (class "Default")
      (node (ref "OK4") (pin "3") (pinfunction "EMIT_3") (pintype "passive"))
      (node (ref "R33") (pin "1") (pinfunction "1_1") (pintype "passive"))
      (node (ref "R38") (pin "1") (pinfunction "1_1") (pintype "passive"))
    )
    (net (code "38") (name "Net-(Q2-PadD)") (class "Default")
      (node (ref "Q2") (pin "D") (pinfunction "D_D") (pintype "passive"))
      (node (ref "Q4") (pin "D") (pinfunction "D_D") (pintype "passive"))
    )
    (net (code "39") (name "Net-(Q3-PadB)") (class "Default")
      (node (ref "Q3") (pin "B") (pinfunction "B_B") (pintype "passive"))
      (node (ref "R18") (pin "1") (pinfunction "1_1") (pintype "passive"))
    )
    (net (code "40") (name "Net-(Q3-PadE)") (class "Default")
      (node (ref "Q3") (pin "E") (pinfunction "E_E") (pintype "passive"))
      (node (ref "R23") (pin "1") (pinfunction "1_1") (pintype "passive"))
      (node (ref "R42") (pin "2") (pinfunction "2_2") (pintype "passive"))
    )
    (net (code "41") (name "Net-(R5-Pad1)") (class "Default")
      (node (ref "R5") (pin "1") (pinfunction "1_1") (pintype "passive"))
      (node (ref "R8") (pin "1") (pinfunction "1_1") (pintype "passive"))
    )
    (net (code "42") (name "Net-(R11-A)") (class "Default")
      (node (ref "R11") (pin "1") (pinfunction "A_1") (pintype "passive"))
      (node (ref "R5") (pin "2") (pinfunction "2_2") (pintype "passive"))
    )
    (net (code "43") (name "Net-(R11-E)") (class "Default")
      (node (ref "R11") (pin "2") (pinfunction "S_2") (pintype "passive"))
      (node (ref "R11") (pin "3") (pinfunction "E_3") (pintype "passive"))
      (node (ref "R15") (pin "2") (pinfunction "2_2") (pintype "passive"))
      (node (ref "R4") (pin "1") (pinfunction "1_1") (pintype "passive"))
      (node (ref "R47") (pin "1") (pinfunction "1_1") (pintype "passive"))
    )
    (net (code "44") (name "Net-(R49-Pad2)") (class "Default")
      (node (ref "R49") (pin "2") (pinfunction "2_2") (pintype "passive"))
      (node (ref "R50") (pin "1") (pinfunction "1_1") (pintype "passive"))
    )
    (net (code "45") (name "Net-(R50-Pad2)") (class "Default")
      (node (ref "R50") (pin "2") (pinfunction "2_2") (pintype "passive"))
      (node (ref "R7") (pin "1") (pinfunction "1_1") (pintype "passive"))
    )
    (net (code "46") (name "Net-(R53-A)") (class "Default")
      (node (ref "R13") (pin "2") (pinfunction "2_2") (pintype "passive"))
      (node (ref "R53") (pin "1") (pinfunction "A_1") (pintype "passive"))
      (node (ref "R9") (pin "1") (pinfunction "1_1") (pintype "passive"))
    )
    (net (code "47") (name "Net-(R53-E)") (class "Default")
      (node (ref "R35") (pin "2") (pinfunction "2_2") (pintype "passive"))
      (node (ref "R45") (pin "1") (pinfunction "1_1") (pintype "passive"))
      (node (ref "R46") (pin "2") (pinfunction "2_2") (pintype "passive"))
      (node (ref "R53") (pin "3") (pinfunction "E_3") (pintype "passive"))
    )
    (net (code "48") (name "Net-(R53-S)") (class "Default")
      (node (ref "C15") (pin "2") (pinfunction "2_2") (pintype "passive"))
      (node (ref "R14") (pin "1") (pinfunction "1_1") (pintype "passive"))
      (node (ref "R53") (pin "2") (pinfunction "S_2") (pintype "passive"))
      (node (ref "R9") (pin "2") (pinfunction "2_2") (pintype "passive"))
    )
    (net (code "49") (name "Net-(R54-A)") (class "Default")
      (node (ref "R39") (pin "1") (pinfunction "1_1") (pintype "passive"))
      (node (ref "R52") (pin "2") (pinfunction "2_2") (pintype "passive"))
      (node (ref "R54") (pin "1") (pinfunction "A_1") (pintype "passive"))
    )
    (net (code "50") (name "Net-(R54-E)") (class "Default")
      (node (ref "R26") (pin "1") (pinfunction "1_1") (pintype "passive"))
      (node (ref "R43") (pin "1") (pinfunction "1_1") (pintype "passive"))
      (node (ref "R54") (pin "3") (pinfunction "E_3") (pintype "passive"))
    )
    (net (code "51") (name "Net-(R54-S)") (class "Default")
      (node (ref "C6") (pin "2") (pinfunction "2_2") (pintype "passive"))
      (node (ref "R41") (pin "2") (pinfunction "2_2") (pintype "passive"))
      (node (ref "R52") (pin "1") (pinfunction "1_1") (pintype "passive"))
      (node (ref "R54") (pin "2") (pinfunction "S_2") (pintype "passive"))
    )
    (net (code "52") (name "Net-(R64-Pad1)") (class "Default")
      (node (ref "R64") (pin "1") (pinfunction "1_1") (pintype "passive"))
      (node (ref "R65") (pin "2") (pinfunction "2_2") (pintype "passive"))
    )
    (net (code "53") (name "Net-(R66-Pad2)") (class "Default")
      (node (ref "R66") (pin "2") (pinfunction "2_2") (pintype "passive"))
      (node (ref "R67") (pin "2") (pinfunction "2_2") (pintype "passive"))
    )
    (net (code "54") (name "Net-(U1-OUT)") (class "Default")
      (node (ref "R16") (pin "2") (pinfunction "2_2") (pintype "passive"))
      (node (ref "U1") (pin "6") (pinfunction "OUT_6") (pintype "output"))
    )
    (net (code "55") (name "Net-(U2-BOOT)") (class "Default")
      (node (ref "C13") (pin "1") (pinfunction "1_1") (pintype "passive"))
      (node (ref "U2") (pin "1") (pinfunction "BOOT_1") (pintype "input"))
    )
    (net (code "56") (name "Net-(U2-COMP)") (class "Default")
      (node (ref "C3") (pin "2") (pinfunction "2_2") (pintype "passive"))
      (node (ref "R2") (pin "1") (pinfunction "1_1") (pintype "passive"))
      (node (ref "U2") (pin "6") (pinfunction "COMP_6") (pintype "input"))
    )
    (net (code "57") (name "Net-(U2-FB)") (class "Default")
      (node (ref "D2") (pin "C") (pinfunction "C_C") (pintype "passive"))
      (node (ref "R15") (pin "1") (pinfunction "1_1") (pintype "passive"))
      (node (ref "U2") (pin "5") (pinfunction "FB_5") (pintype "input"))
    )
    (net (code "58") (name "Net-(U2-RT{slash}CL)") (class "Default")
      (node (ref "R1") (pin "2") (pinfunction "2_2") (pintype "passive"))
      (node (ref "U2") (pin "4") (pinfunction "RT/CL_4") (pintype "input"))
    )
    (net (code "59") (name "Net-(U3-OUT)") (class "Default")
      (node (ref "R12") (pin "1") (pinfunction "1_1") (pintype "passive"))
      (node (ref "U3") (pin "6") (pinfunction "OUT_6") (pintype "output"))
    )
    (net (code "60") (name "Net-(U4-C)") (class "Default")
      (node (ref "C17") (pin "2") (pinfunction "2_2") (pintype "passive"))
      (node (ref "R22") (pin "2") (pinfunction "2_2") (pintype "passive"))
      (node (ref "R26") (pin "2") (pinfunction "2_2") (pintype "passive"))
      (node (ref "U4") (pin "1") (pinfunction "C_1") (pintype "passive"))
      (node (ref "U4") (pin "2") (pinfunction "R_2") (pintype "passive"))
    )
    (net (code "61") (name "Net-(U6-BOOT)") (class "Default")
      (node (ref "C36") (pin "1") (pinfunction "1_1") (pintype "passive"))
      (node (ref "U6") (pin "1") (pinfunction "BOOT_1") (pintype "input"))
    )
    (net (code "62") (name "Net-(U6-COMP)") (class "Default")
      (node (ref "C33") (pin "2") (pinfunction "2_2") (pintype "passive"))
      (node (ref "R61") (pin "1") (pinfunction "1_1") (pintype "passive"))
      (node (ref "U6") (pin "6") (pinfunction "COMP_6") (pintype "input"))
    )
    (net (code "63") (name "Net-(U6-FB)") (class "Default")
      (node (ref "R63") (pin "1") (pinfunction "1_1") (pintype "passive"))
      (node (ref "R64") (pin "2") (pinfunction "2_2") (pintype "passive"))
      (node (ref "U6") (pin "5") (pinfunction "FB_5") (pintype "input"))
    )
    (net (code "64") (name "Net-(U6-RT{slash}CL)") (class "Default")
      (node (ref "R66") (pin "1") (pinfunction "1_1") (pintype "passive"))
      (node (ref "U6") (pin "4") (pinfunction "RT/CL_4") (pintype "input"))
    )
    (net (code "65") (name "Net-(X1A-KL)") (class "Default")
      (node (ref "C20") (pin "2") (pinfunction "2_2") (pintype "passive"))
      (node (ref "C25") (pin "1") (pinfunction "1_1") (pintype "passive"))
      (node (ref "X1") (pin "1") (pinfunction "KL_1") (pintype "passive"))
    )
    (net (code "66") (name "Net-(X1B-KL)") (class "Default")
      (node (ref "R36") (pin "2") (pinfunction "2_2") (pintype "passive"))
      (node (ref "X1") (pin "2") (pinfunction "KL_2") (pintype "passive"))
    )
    (net (code "67") (name "Net-(X3B-KL)") (class "Default")
      (node (ref "R44") (pin "1") (pinfunction "1_1") (pintype "passive"))
      (node (ref "X3") (pin "2") (pinfunction "KL_2") (pintype "passive"))
    )
    (net (code "68") (name "OUT+") (class "Default")
      (node (ref "C19") (pin "1") (pinfunction "1_1") (pintype "passive"))
      (node (ref "C25") (pin "2") (pinfunction "2_2") (pintype "passive"))
      (node (ref "D4") (pin "C") (pinfunction "C_C") (pintype "passive"))
      (node (ref "D5") (pin "C") (pinfunction "C_C") (pintype "passive"))
      (node (ref "D6") (pin "C") (pinfunction "C_C") (pintype "passive"))
      (node (ref "D9") (pin "1") (pinfunction "K_1") (pintype "passive"))
      (node (ref "Q1") (pin "D") (pinfunction "D_D") (pintype "passive"))
      (node (ref "Q2") (pin "S") (pinfunction "S_S") (pintype "passive"))
      (node (ref "R24") (pin "2") (pinfunction "2_2") (pintype "passive"))
      (node (ref "R3") (pin "2") (pinfunction "2_2") (pintype "passive"))
      (node (ref "R37") (pin "2") (pinfunction "2_2") (pintype "passive"))
      (node (ref "R44") (pin "2") (pinfunction "2_2") (pintype "passive"))
      (node (ref "X2") (pin "6") (pinfunction "KL_6") (pintype "passive"))
    )
    (net (code "69") (name "OUTONOFFPB0") (class "Default")
      (node (ref "R28") (pin "2") (pinfunction "2_2") (pintype "passive"))
      (node (ref "R29") (pin "1") (pinfunction "1_1") (pintype "passive"))
      (node (ref "X2") (pin "9") (pinfunction "KL_9") (pintype "passive"))
    )
    (net (code "70") (name "PA1IL") (class "Default")
      (node (ref "R12") (pin "2") (pinfunction "2_2") (pintype "passive"))
      (node (ref "X2") (pin "1") (pinfunction "KL_1") (pintype "passive"))
    )
    (net (code "71") (name "PA2IO") (class "Default")
      (node (ref "R16") (pin "1") (pinfunction "1_1") (pintype "passive"))
      (node (ref "X2") (pin "5") (pinfunction "KL_5") (pintype "passive"))
    )
    (net (code "72") (name "V+") (class "Default")
      (node (ref "C20") (pin "1") (pinfunction "1_1") (pintype "passive"))
      (node (ref "D11") (pin "2") (pinfunction "A_2") (pintype "passive"))
      (node (ref "D4") (pin "A") (pinfunction "A_A") (pintype "passive"))
      (node (ref "OK1") (pin "4") (pinfunction "COL_4") (pintype "passive"))
      (node (ref "OK2") (pin "4") (pinfunction "COL_4") (pintype "passive"))
      (node (ref "OK4") (pin "4") (pinfunction "COL_4") (pintype "passive"))
      (node (ref "R37") (pin "1") (pinfunction "1_1") (pintype "passive"))
    )
    (net (code "73") (name "unconnected-(U2-EN-Pad3)") (class "Default")
      (node (ref "U2") (pin "3") (pinfunction "EN_3") (pintype "input"))
    )
    (net (code "74") (name "unconnected-(U6-EN-Pad3)") (class "Default")
      (node (ref "U6") (pin "3") (pinfunction "EN_3") (pintype "input"))
    )
  )
)
